# schemetic.net
KiCad netlist of a schematic drawn in Altium Designer
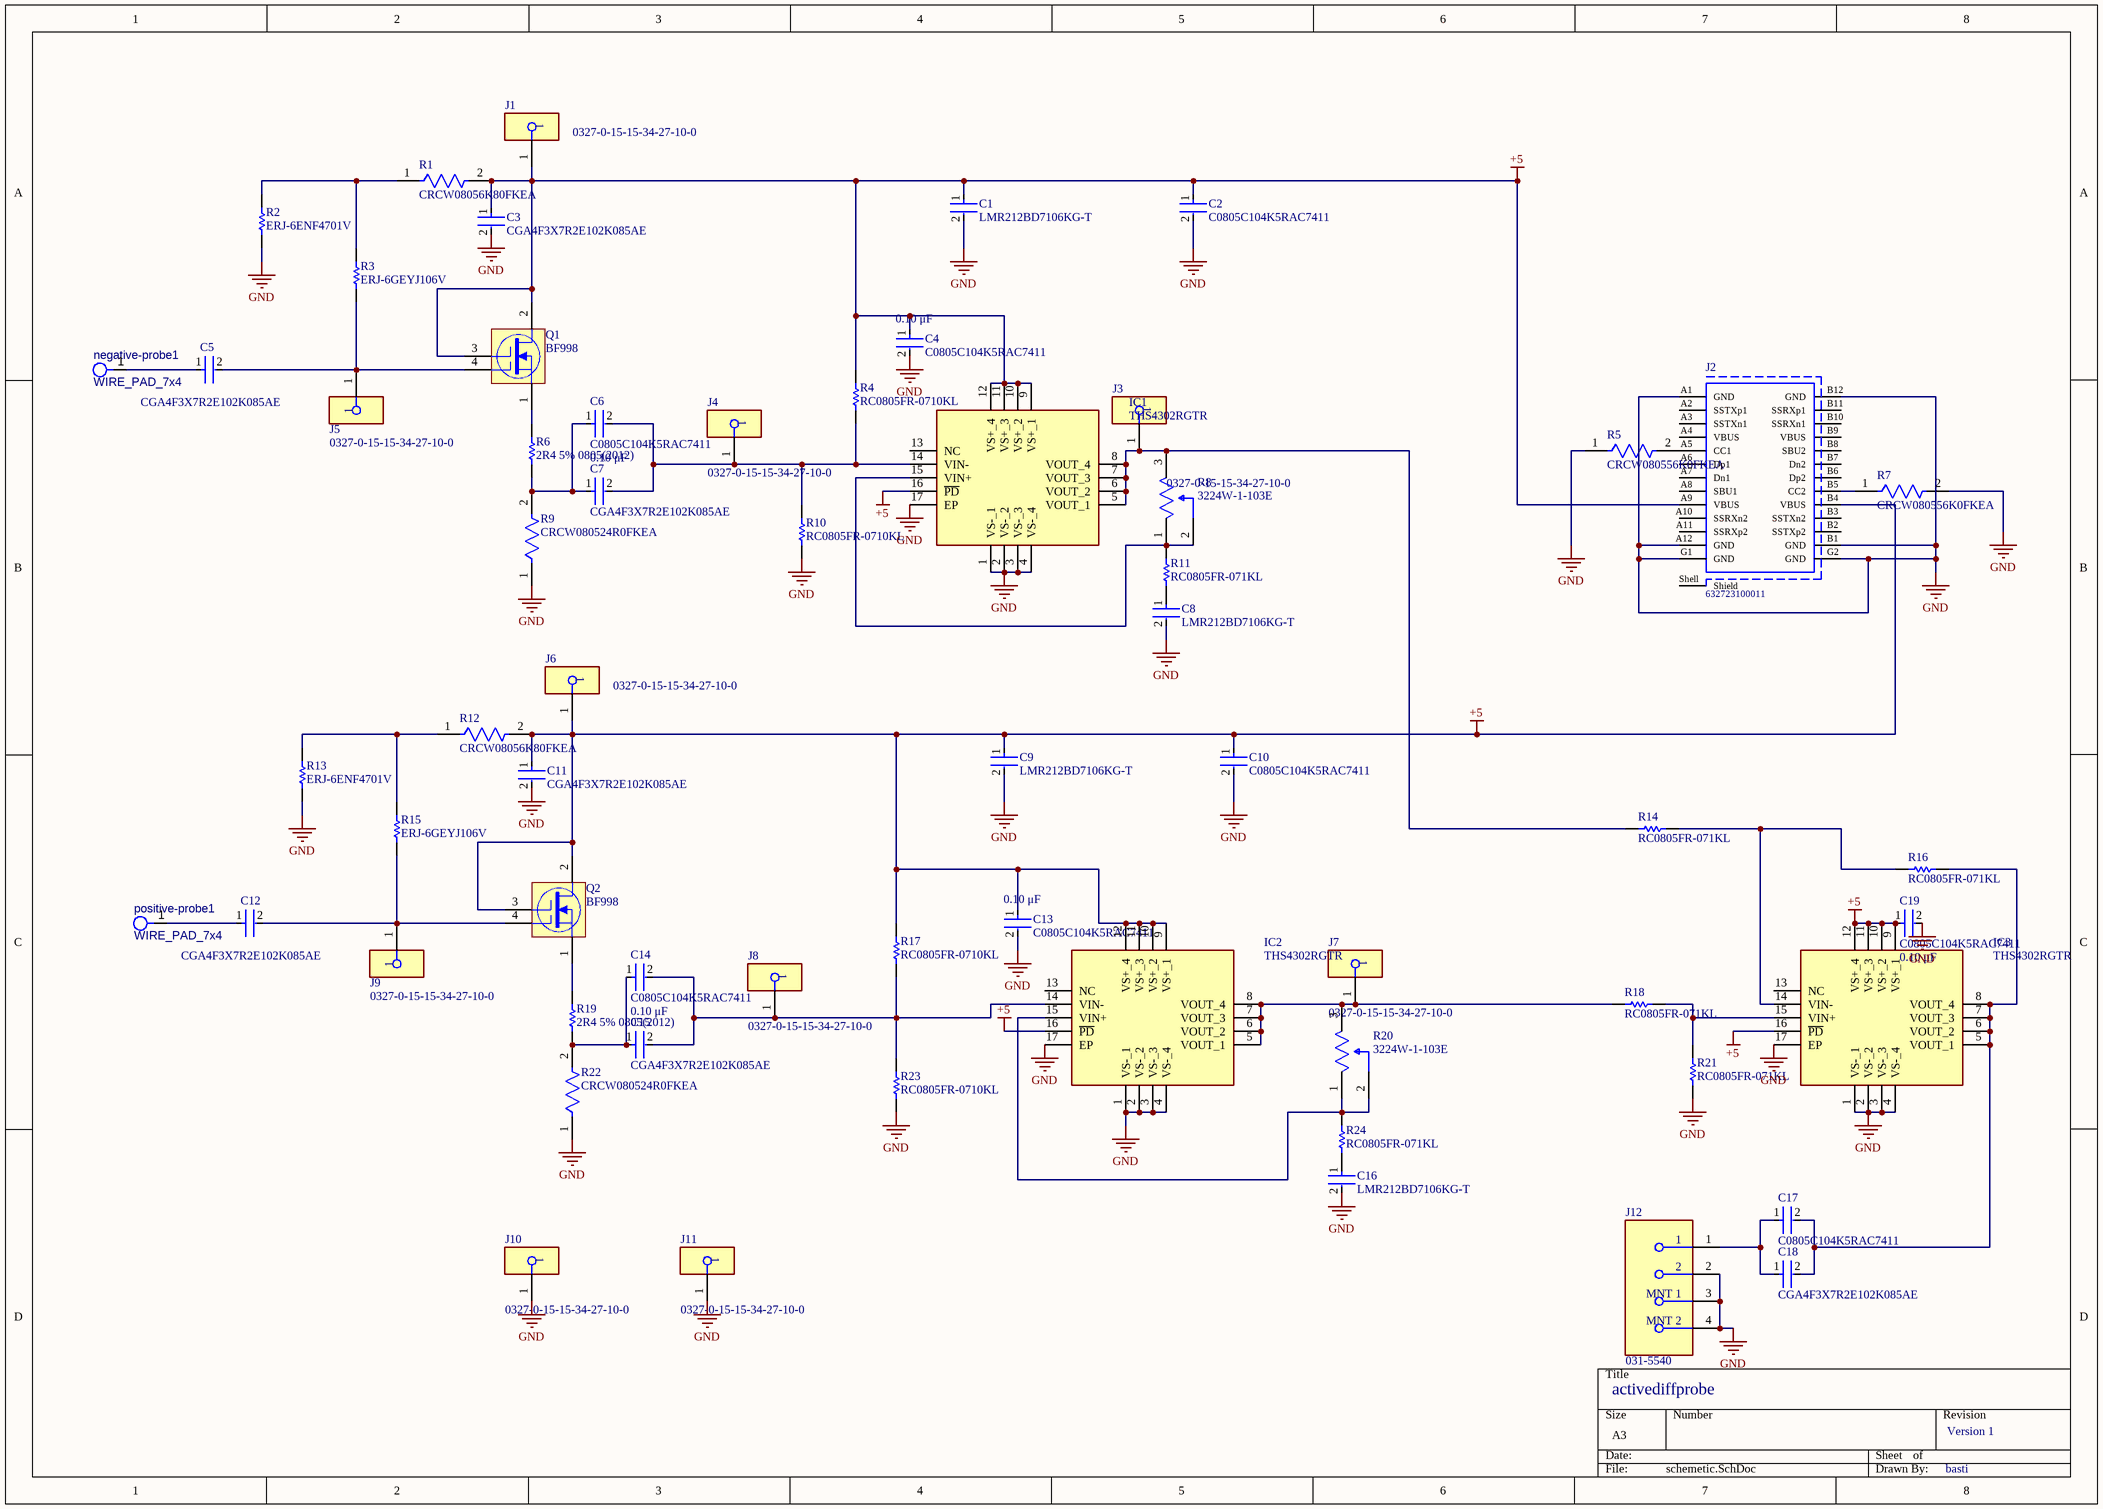
[diagram p0: schemetic.SchDoc]

(export (version "E")
  (design (tool "Eeschema 10.0.6"))
  (components
    (comp (ref "C1")
      (value "LMR212BD7106KG-T")
      (footprint "FP-0805-L_2_0_0_2-W_1_25-IPC_C")
      (description "Multilayer Ceramic Capacitor 10uF 10V X7T 10% SMD 0805 Automotive T/R")
      (libsource (lib "Altium Content Vault") (part "02cd4be3c70576c341d710602a673aa"))
    )
    (comp (ref "C2")
      (value "C0805C104K5RAC7411")
      (footprint "FP-C0805C-DN-MFG")
      (description "C0805 0.10 μF X7R 30ppm/°C 10.00% 50 V")
      (fields (field (name "MANUFACTURER") "KEMET") (field (name "TOLERANCE") "0.1"))
      (libsource (lib "Altium Content Vault") (part "b4654b650e69147ec39a6b967a45e02"))
    )
    (comp (ref "C3")
      (value "CGA4F3X7R2E102K085AE")
      (footprint "FP-CGA4J-IPC_B")
      (description "Cap Ceramic 1nF 250V X7R 10% Pad SMD 0805 +125°C Automotive T/R")
      (fields (field (name "TOLERANCE") "10%"))
      (libsource (lib "Altium Content Vault") (part "b4654b650e69147ec39a6b967a45e02"))
    )
    (comp (ref "C4")
      (value "C0805C104K5RAC7411")
      (footprint "FP-C0805C-DN-MFG")
      (description "C0805 0.10 μF X7R 30ppm/°C 10.00% 50 V")
      (fields
        (field (name "MANUFACTURER") "KEMET")
        (field (name "TOLERANCE") "0.1")
        (field (name "ALTIUM_VALUE") "0.10 μF")
      )
      (libsource (lib "Altium Content Vault") (part "b4654b650e69147ec39a6b967a45e02"))
    )
    (comp (ref "C5")
      (value "CGA4F3X7R2E102K085AE")
      (footprint "FP-CGA4J-IPC_B")
      (description "Cap Ceramic 1nF 250V X7R 10% Pad SMD 0805 +125°C Automotive T/R")
      (fields (field (name "TOLERANCE") "10%"))
      (libsource (lib "Altium Content Vault") (part "b4654b650e69147ec39a6b967a45e02"))
    )
    (comp (ref "C6")
      (value "C0805C104K5RAC7411")
      (footprint "FP-C0805C-DN-MFG")
      (description "C0805 0.10 μF X7R 30ppm/°C 10.00% 50 V")
      (fields
        (field (name "MANUFACTURER") "KEMET")
        (field (name "TOLERANCE") "0.1")
        (field (name "ALTIUM_VALUE") "0.10 μF")
      )
      (libsource (lib "Altium Content Vault") (part "b4654b650e69147ec39a6b967a45e02"))
    )
    (comp (ref "C7")
      (value "CGA4F3X7R2E102K085AE")
      (footprint "FP-CGA4J-IPC_B")
      (description "Cap Ceramic 1nF 250V X7R 10% Pad SMD 0805 +125°C Automotive T/R")
      (fields (field (name "TOLERANCE") "10%"))
      (libsource (lib "Altium Content Vault") (part "b4654b650e69147ec39a6b967a45e02"))
    )
    (comp (ref "C8")
      (value "LMR212BD7106KG-T")
      (footprint "FP-0805-L_2_0_0_2-W_1_25-IPC_C")
      (description "Multilayer Ceramic Capacitor 10uF 10V X7T 10% SMD 0805 Automotive T/R")
      (libsource (lib "Altium Content Vault") (part "02cd4be3c70576c341d710602a673aa"))
    )
    (comp (ref "C9")
      (value "LMR212BD7106KG-T")
      (footprint "FP-0805-L_2_0_0_2-W_1_25-IPC_C")
      (description "Multilayer Ceramic Capacitor 10uF 10V X7T 10% SMD 0805 Automotive T/R")
      (libsource (lib "Altium Content Vault") (part "02cd4be3c70576c341d710602a673aa"))
    )
    (comp (ref "C10")
      (value "C0805C104K5RAC7411")
      (footprint "FP-C0805C-DN-MFG")
      (description "C0805 0.10 μF X7R 30ppm/°C 10.00% 50 V")
      (fields (field (name "MANUFACTURER") "KEMET") (field (name "TOLERANCE") "0.1"))
      (libsource (lib "Altium Content Vault") (part "b4654b650e69147ec39a6b967a45e02"))
    )
    (comp (ref "C11")
      (value "CGA4F3X7R2E102K085AE")
      (footprint "FP-CGA4J-IPC_B")
      (description "Cap Ceramic 1nF 250V X7R 10% Pad SMD 0805 +125°C Automotive T/R")
      (fields (field (name "TOLERANCE") "10%"))
      (libsource (lib "Altium Content Vault") (part "b4654b650e69147ec39a6b967a45e02"))
    )
    (comp (ref "C12")
      (value "CGA4F3X7R2E102K085AE")
      (footprint "FP-CGA4J-IPC_B")
      (description "Cap Ceramic 1nF 250V X7R 10% Pad SMD 0805 +125°C Automotive T/R")
      (fields (field (name "TOLERANCE") "10%"))
      (libsource (lib "Altium Content Vault") (part "b4654b650e69147ec39a6b967a45e02"))
    )
    (comp (ref "C13")
      (value "C0805C104K5RAC7411")
      (footprint "FP-C0805C-DN-MFG")
      (description "C0805 0.10 μF X7R 30ppm/°C 10.00% 50 V")
      (fields
        (field (name "MANUFACTURER") "KEMET")
        (field (name "TOLERANCE") "0.1")
        (field (name "ALTIUM_VALUE") "0.10 μF")
      )
      (libsource (lib "Altium Content Vault") (part "b4654b650e69147ec39a6b967a45e02"))
    )
    (comp (ref "C14")
      (value "C0805C104K5RAC7411")
      (footprint "FP-C0805C-DN-MFG")
      (description "C0805 0.10 μF X7R 30ppm/°C 10.00% 50 V")
      (fields
        (field (name "MANUFACTURER") "KEMET")
        (field (name "TOLERANCE") "0.1")
        (field (name "ALTIUM_VALUE") "0.10 μF")
      )
      (libsource (lib "Altium Content Vault") (part "b4654b650e69147ec39a6b967a45e02"))
    )
    (comp (ref "C15")
      (value "CGA4F3X7R2E102K085AE")
      (footprint "FP-CGA4J-IPC_B")
      (description "Cap Ceramic 1nF 250V X7R 10% Pad SMD 0805 +125°C Automotive T/R")
      (fields (field (name "TOLERANCE") "10%"))
      (libsource (lib "Altium Content Vault") (part "b4654b650e69147ec39a6b967a45e02"))
    )
    (comp (ref "C16")
      (value "LMR212BD7106KG-T")
      (footprint "FP-0805-L_2_0_0_2-W_1_25-IPC_C")
      (description "Multilayer Ceramic Capacitor 10uF 10V X7T 10% SMD 0805 Automotive T/R")
      (libsource (lib "Altium Content Vault") (part "02cd4be3c70576c341d710602a673aa"))
    )
    (comp (ref "C17")
      (value "C0805C104K5RAC7411")
      (footprint "FP-C0805C-DN-MFG")
      (description "C0805 0.10 μF X7R 30ppm/°C 10.00% 50 V")
      (fields (field (name "MANUFACTURER") "KEMET") (field (name "TOLERANCE") "0.1"))
      (libsource (lib "Altium Content Vault") (part "b4654b650e69147ec39a6b967a45e02"))
    )
    (comp (ref "C18")
      (value "CGA4F3X7R2E102K085AE")
      (footprint "FP-CGA4J-IPC_B")
      (description "Cap Ceramic 1nF 250V X7R 10% Pad SMD 0805 +125°C Automotive T/R")
      (fields (field (name "TOLERANCE") "10%"))
      (libsource (lib "Altium Content Vault") (part "b4654b650e69147ec39a6b967a45e02"))
    )
    (comp (ref "C19")
      (value "C0805C104K5RAC7411")
      (footprint "FP-C0805C-DN-MFG")
      (description "C0805 0.10 μF X7R 30ppm/°C 10.00% 50 V")
      (fields
        (field (name "MANUFACTURER") "KEMET")
        (field (name "TOLERANCE") "0.1")
        (field (name "ALTIUM_VALUE") "0.10 μF")
      )
      (libsource (lib "Altium Content Vault") (part "b4654b650e69147ec39a6b967a45e02"))
    )
    (comp (ref "IC1")
      (value "THS4302RGTR")
      (footprint "SamacSys:QFN50P300X300X100-17N-D")
      (description "Integrated Circuit")
      (libsource (lib "*") (part "THS4302RGTR"))
    )
    (comp (ref "IC2")
      (value "THS4302RGTR")
      (footprint "SamacSys:QFN50P300X300X100-17N-D")
      (description "Integrated Circuit")
      (libsource (lib "*") (part "THS4302RGTR"))
    )
    (comp (ref "IC3")
      (value "THS4302RGTR")
      (footprint "SamacSys:QFN50P300X300X100-17N-D")
      (description "Integrated Circuit")
      (libsource (lib "*") (part "THS4302RGTR"))
    )
    (comp (ref "J1")
      (value "0327-0-15-15-34-27-10-0")
      (footprint "FP-0327-0-15-15-34-27-10-MFG")
      (description "CONN PIN RCPT .032-.046 SOLDER")
      (libsource (lib "Altium Content Vault") (part "c5c826e0c4b67fe3b42ef77f2d4decc"))
    )
    (comp (ref "J2")
      (value "632723100011")
      (footprint "632723100011")
      (description "USB 3.1 Type C Receptacle WR-COM, Horizontal, SMT / THT")
      (fields (field (name "MANUFACTURER") "Wurth Elektronik") (field (name "PUBLISHER") "WurthElektronik"))
      (libsource (lib "Altium Content Vault") (part "WE-632723X00011"))
    )
    (comp (ref "J3")
      (value "0327-0-15-15-34-27-10-0")
      (footprint "FP-0327-0-15-15-34-27-10-MFG")
      (description "CONN PIN RCPT .032-.046 SOLDER")
      (libsource (lib "Altium Content Vault") (part "c5c826e0c4b67fe3b42ef77f2d4decc"))
    )
    (comp (ref "J4")
      (value "0327-0-15-15-34-27-10-0")
      (footprint "FP-0327-0-15-15-34-27-10-MFG")
      (description "CONN PIN RCPT .032-.046 SOLDER")
      (libsource (lib "Altium Content Vault") (part "c5c826e0c4b67fe3b42ef77f2d4decc"))
    )
    (comp (ref "J5")
      (value "0327-0-15-15-34-27-10-0")
      (footprint "FP-0327-0-15-15-34-27-10-MFG")
      (description "CONN PIN RCPT .032-.046 SOLDER")
      (libsource (lib "") (part "c5c826e0c4b67fe3b42ef77f2d4decc_1"))
    )
    (comp (ref "J6")
      (value "0327-0-15-15-34-27-10-0")
      (footprint "FP-0327-0-15-15-34-27-10-MFG")
      (description "CONN PIN RCPT .032-.046 SOLDER")
      (libsource (lib "Altium Content Vault") (part "c5c826e0c4b67fe3b42ef77f2d4decc"))
    )
    (comp (ref "J7")
      (value "0327-0-15-15-34-27-10-0")
      (footprint "FP-0327-0-15-15-34-27-10-MFG")
      (description "CONN PIN RCPT .032-.046 SOLDER")
      (libsource (lib "Altium Content Vault") (part "c5c826e0c4b67fe3b42ef77f2d4decc"))
    )
    (comp (ref "J8")
      (value "0327-0-15-15-34-27-10-0")
      (footprint "FP-0327-0-15-15-34-27-10-MFG")
      (description "CONN PIN RCPT .032-.046 SOLDER")
      (libsource (lib "Altium Content Vault") (part "c5c826e0c4b67fe3b42ef77f2d4decc"))
    )
    (comp (ref "J9")
      (value "0327-0-15-15-34-27-10-0")
      (footprint "FP-0327-0-15-15-34-27-10-MFG")
      (description "CONN PIN RCPT .032-.046 SOLDER")
      (libsource (lib "") (part "c5c826e0c4b67fe3b42ef77f2d4decc_1"))
    )
    (comp (ref "J10")
      (value "0327-0-15-15-34-27-10-0")
      (footprint "FP-0327-0-15-15-34-27-10-MFG")
      (description "CONN PIN RCPT .032-.046 SOLDER")
      (libsource (lib "Altium Content Vault") (part "c5c826e0c4b67fe3b42ef77f2d4decc"))
    )
    (comp (ref "J11")
      (value "0327-0-15-15-34-27-10-0")
      (footprint "FP-0327-0-15-15-34-27-10-MFG")
      (description "CONN PIN RCPT .032-.046 SOLDER")
      (libsource (lib "Altium Content Vault") (part "c5c826e0c4b67fe3b42ef77f2d4decc"))
    )
    (comp (ref "J12")
      (value "031-5540")
      (footprint "FP-031-5540-MFG")
      (description "CONN BNC RCPT R/A 50 OHM PCB")
      (fields
        (field (name "OCTOPART") "https://octopart.com/031-5540-amphenol+rf-49742301")
        (field (name "MANUFACTURER") "Amphenol RF")
      )
      (libsource (lib "Altium Content Vault") (part "c4223d6e67c9a5a609df11ee682ef75"))
    )
    (comp (ref "negative-probe1")
      (value "WIRE_PAD_7x4")
      (footprint "WIRE_PAD_7x4-Footprint-1")
      (description "SMD WIRE PAD 7 x 4 mm")
      (libsource (lib "Joel Rupp") (part "CMP-001-0023-7"))
    )
    (comp (ref "positive-probe1")
      (value "WIRE_PAD_7x4")
      (footprint "WIRE_PAD_7x4-Footprint-1")
      (description "SMD WIRE PAD 7 x 4 mm")
      (libsource (lib "Joel Rupp") (part "CMP-001-0023-7"))
    )
    (comp (ref "Q1")
      (value "BF998")
      (footprint "INF-SOT143-4-1_V")
      (description "Silicon N-Channel MOSFET Tetrode, 30 mA ID, 20 dB Gp, SOT143-4-1, Green")
      (fields (field (name "MANUFACTURER") "Infineon"))
      (libsource (lib "Altium Content Vault") (part "INF-BF998-4"))
    )
    (comp (ref "Q2")
      (value "BF998")
      (footprint "INF-SOT143-4-1_V")
      (description "Silicon N-Channel MOSFET Tetrode, 30 mA ID, 20 dB Gp, SOT143-4-1, Green")
      (fields (field (name "MANUFACTURER") "Infineon"))
      (libsource (lib "Altium Content Vault") (part "INF-BF998-4"))
    )
    (comp (ref "R1")
      (value "CRCW08056K80FKEA")
      (footprint "FP-CRCW0805-e3-IPC_A")
      (description "RES Thick Film, 6.8kΩ, 1%, 0.125W, 100ppm/°C, 0805")
      (fields (field (name "TOLERANCE") "1%"))
      (libsource (lib "Altium Content Vault") (part "1029c3af85768c4190bb7ad29bc67b5"))
    )
    (comp (ref "R2")
      (value "ERJ-6ENF4701V")
      (footprint "RESC2013X70X40NL20T20")
      (description "Chip Resistor, 4.7 KOhm, +/- 1%, 0.125 W, -55 to 155 degC, 0805 (2012 Metric), RoHS, Tape and Reel")
      (fields (field (name "MANUFACTURER") "Panasonic"))
      (libsource (lib "Altium Content Vault") (part "RES-2"))
    )
    (comp (ref "R3")
      (value "ERJ-6GEYJ106V")
      (footprint "RESC2013X70X40LL20T20")
      (description "10MOhm")
      (fields (field (name "MANUFACTURER") "Panasonic"))
      (libsource (lib "Altium Content Vault") (part "RES"))
    )
    (comp (ref "R4")
      (value "RC0805FR-0710KL")
      (footprint "RESC2013X60X35NL10T20")
      (description "Chip Resistor, 10 KOhm, +/- 1%, 0.125 W, -55 to 155 degC, 0805 (2012 Metric), RoHS, Tape and Reel")
      (fields (field (name "MANUFACTURER") "Yageo"))
      (libsource (lib "Altium Content Vault") (part "RES-2"))
    )
    (comp (ref "R5")
      (value "CRCW080556K0FKEA")
      (footprint "FP-CRCW0805-e3-IPC_B")
      (description "RES Thick Film, 56kΩ, 1%, 0.125W, 100ppm/°C, 0805")
      (fields (field (name "TOLERANCE") "1%"))
      (libsource (lib "Altium Content Vault") (part "1029c3af85768c4190bb7ad29bc67b5"))
    )
    (comp (ref "R6")
      (value "2R4 5% 0805(2012)")
      (footprint "RESC0805(2012)_L")
      (description "2R4 0.125W 5% 0805 (2012 Metric)  SMD")
      (fields (field (name "POWER") "0.125 W") (field (name "TOLERANCE") "5 %"))
      (libsource (lib "Altium Content Vault") (part "RES"))
    )
    (comp (ref "R7")
      (value "CRCW080556K0FKEA")
      (footprint "FP-CRCW0805-e3-IPC_B")
      (description "RES Thick Film, 56kΩ, 1%, 0.125W, 100ppm/°C, 0805")
      (fields (field (name "TOLERANCE") "1%"))
      (libsource (lib "Altium Content Vault") (part "1029c3af85768c4190bb7ad29bc67b5"))
    )
    (comp (ref "R8")
      (value "3224W-1-103E")
      (footprint "FP-3224W-MFG")
      (description "TRIMMER 10K OHM 0.25W J LEAD TOP")
      (fields (field (name "TOLERANCE") "10%") (field (name "MANUFACTURER") "Bourns"))
      (libsource (lib "Altium Content Vault") (part "83d3d349ed884d1db45cec512f27eb6"))
    )
    (comp (ref "R9")
      (value "CRCW080524R0FKEA")
      (footprint "FP-CRCW0805-e3-MFG")
      (description "RES Thick Film, 24Ω, 1%, 0.125W, 100ppm/°C, 0805")
      (fields (field (name "TOLERANCE") "1%"))
      (libsource (lib "Altium Content Vault") (part "1029c3af85768c4190bb7ad29bc67b5"))
    )
    (comp (ref "R10")
      (value "RC0805FR-0710KL")
      (footprint "RESC2013X60X35NL10T20")
      (description "Chip Resistor, 10 KOhm, +/- 1%, 0.125 W, -55 to 155 degC, 0805 (2012 Metric), RoHS, Tape and Reel")
      (fields (field (name "MANUFACTURER") "Yageo"))
      (libsource (lib "Altium Content Vault") (part "RES-2"))
    )
    (comp (ref "R11")
      (value "RC0805FR-071KL")
      (footprint "RESC2013X60X35ML10T20")
      (description "Chip Resistor, 1 KOhm, +/- 1%, 125 mW, -55 to 155 degC, 0805 (2012 Metric), RoHS, Tape and Reel")
      (fields (field (name "TOLERANCE") "1%") (field (name "MANUFACTURER") "Yageo"))
      (libsource (lib "Altium Content Vault") (part "RES-2"))
    )
    (comp (ref "R12")
      (value "CRCW08056K80FKEA")
      (footprint "FP-CRCW0805-e3-IPC_A")
      (description "RES Thick Film, 6.8kΩ, 1%, 0.125W, 100ppm/°C, 0805")
      (fields (field (name "TOLERANCE") "1%"))
      (libsource (lib "Altium Content Vault") (part "1029c3af85768c4190bb7ad29bc67b5"))
    )
    (comp (ref "R13")
      (value "ERJ-6ENF4701V")
      (footprint "RESC2013X70X40NL20T20")
      (description "Chip Resistor, 4.7 KOhm, +/- 1%, 0.125 W, -55 to 155 degC, 0805 (2012 Metric), RoHS, Tape and Reel")
      (fields (field (name "MANUFACTURER") "Panasonic"))
      (libsource (lib "Altium Content Vault") (part "RES-2"))
    )
    (comp (ref "R14")
      (value "RC0805FR-071KL")
      (footprint "RESC2013X60X35ML10T20")
      (description "Chip Resistor, 1 KOhm, +/- 1%, 125 mW, -55 to 155 degC, 0805 (2012 Metric), RoHS, Tape and Reel")
      (fields (field (name "TOLERANCE") "1%") (field (name "MANUFACTURER") "Yageo"))
      (libsource (lib "Altium Content Vault") (part "RES-2"))
    )
    (comp (ref "R15")
      (value "ERJ-6GEYJ106V")
      (footprint "RESC2013X70X40LL20T20")
      (description "10MOhm")
      (fields (field (name "MANUFACTURER") "Panasonic"))
      (libsource (lib "Altium Content Vault") (part "RES"))
    )
    (comp (ref "R16")
      (value "RC0805FR-071KL")
      (footprint "RESC2013X60X35ML10T20")
      (description "Chip Resistor, 1 KOhm, +/- 1%, 125 mW, -55 to 155 degC, 0805 (2012 Metric), RoHS, Tape and Reel")
      (fields (field (name "TOLERANCE") "1%") (field (name "MANUFACTURER") "Yageo"))
      (libsource (lib "Altium Content Vault") (part "RES-2"))
    )
    (comp (ref "R17")
      (value "RC0805FR-0710KL")
      (footprint "RESC2013X60X35NL10T20")
      (description "Chip Resistor, 10 KOhm, +/- 1%, 0.125 W, -55 to 155 degC, 0805 (2012 Metric), RoHS, Tape and Reel")
      (fields (field (name "MANUFACTURER") "Yageo"))
      (libsource (lib "Altium Content Vault") (part "RES-2"))
    )
    (comp (ref "R18")
      (value "RC0805FR-071KL")
      (footprint "RESC2013X60X35ML10T20")
      (description "Chip Resistor, 1 KOhm, +/- 1%, 125 mW, -55 to 155 degC, 0805 (2012 Metric), RoHS, Tape and Reel")
      (fields (field (name "TOLERANCE") "1%") (field (name "MANUFACTURER") "Yageo"))
      (libsource (lib "Altium Content Vault") (part "RES-2"))
    )
    (comp (ref "R19")
      (value "2R4 5% 0805(2012)")
      (footprint "RESC0805(2012)_L")
      (description "2R4 0.125W 5% 0805 (2012 Metric)  SMD")
      (fields (field (name "POWER") "0.125 W") (field (name "TOLERANCE") "5 %"))
      (libsource (lib "Altium Content Vault") (part "RES"))
    )
    (comp (ref "R20")
      (value "3224W-1-103E")
      (footprint "FP-3224W-MFG")
      (description "TRIMMER 10K OHM 0.25W J LEAD TOP")
      (fields (field (name "TOLERANCE") "10%") (field (name "MANUFACTURER") "Bourns"))
      (libsource (lib "Altium Content Vault") (part "83d3d349ed884d1db45cec512f27eb6"))
    )
    (comp (ref "R21")
      (value "RC0805FR-071KL")
      (footprint "RESC2013X60X35ML10T20")
      (description "Chip Resistor, 1 KOhm, +/- 1%, 125 mW, -55 to 155 degC, 0805 (2012 Metric), RoHS, Tape and Reel")
      (fields (field (name "TOLERANCE") "1%") (field (name "MANUFACTURER") "Yageo"))
      (libsource (lib "Altium Content Vault") (part "RES-2"))
    )
    (comp (ref "R22")
      (value "CRCW080524R0FKEA")
      (footprint "FP-CRCW0805-e3-MFG")
      (description "RES Thick Film, 24Ω, 1%, 0.125W, 100ppm/°C, 0805")
      (fields (field (name "TOLERANCE") "1%"))
      (libsource (lib "Altium Content Vault") (part "1029c3af85768c4190bb7ad29bc67b5"))
    )
    (comp (ref "R23")
      (value "RC0805FR-0710KL")
      (footprint "RESC2013X60X35NL10T20")
      (description "Chip Resistor, 10 KOhm, +/- 1%, 0.125 W, -55 to 155 degC, 0805 (2012 Metric), RoHS, Tape and Reel")
      (fields (field (name "MANUFACTURER") "Yageo"))
      (libsource (lib "Altium Content Vault") (part "RES-2"))
    )
    (comp (ref "R24")
      (value "RC0805FR-071KL")
      (footprint "RESC2013X60X35ML10T20")
      (description "Chip Resistor, 1 KOhm, +/- 1%, 125 mW, -55 to 155 degC, 0805 (2012 Metric), RoHS, Tape and Reel")
      (fields (field (name "TOLERANCE") "1%") (field (name "MANUFACTURER") "Yageo"))
      (libsource (lib "Altium Content Vault") (part "RES-2"))
    )
  )
  (nets
    (net (code "1") (name "+5") (class "Default")
      (node (ref "C1") (pin "1") (pinfunction "1_1") (pintype "passive"))
      (node (ref "C10") (pin "1") (pinfunction "1_1") (pintype "passive"))
      (node (ref "C11") (pin "1") (pinfunction "1_1") (pintype "passive"))
      (node (ref "C13") (pin "1") (pinfunction "1_1") (pintype "passive"))
      (node (ref "C19") (pin "1") (pinfunction "1_1") (pintype "passive"))
      (node (ref "C2") (pin "1") (pinfunction "1_1") (pintype "passive"))
      (node (ref "C3") (pin "1") (pinfunction "1_1") (pintype "passive"))
      (node (ref "C4") (pin "1") (pinfunction "1_1") (pintype "passive"))
      (node (ref "C9") (pin "1") (pinfunction "1_1") (pintype "passive"))
      (node (ref "IC1") (pin "10") (pinfunction "VS+_2_10") (pintype "passive"))
      (node (ref "IC1") (pin "11") (pinfunction "VS+_3_11") (pintype "passive"))
      (node (ref "IC1") (pin "12") (pinfunction "VS+_4_12") (pintype "passive"))
      (node (ref "IC1") (pin "16") (pinfunction "~{PD}_16") (pintype "passive"))
      (node (ref "IC1") (pin "9") (pinfunction "VS+_1_9") (pintype "passive"))
      (node (ref "IC2") (pin "10") (pinfunction "VS+_2_10") (pintype "passive"))
      (node (ref "IC2") (pin "11") (pinfunction "VS+_3_11") (pintype "passive"))
      (node (ref "IC2") (pin "12") (pinfunction "VS+_4_12") (pintype "passive"))
      (node (ref "IC2") (pin "16") (pinfunction "~{PD}_16") (pintype "passive"))
      (node (ref "IC2") (pin "9") (pinfunction "VS+_1_9") (pintype "passive"))
      (node (ref "IC3") (pin "10") (pinfunction "VS+_2_10") (pintype "passive"))
      (node (ref "IC3") (pin "11") (pinfunction "VS+_3_11") (pintype "passive"))
      (node (ref "IC3") (pin "12") (pinfunction "VS+_4_12") (pintype "passive"))
      (node (ref "IC3") (pin "16") (pinfunction "~{PD}_16") (pintype "passive"))
      (node (ref "IC3") (pin "9") (pinfunction "VS+_1_9") (pintype "passive"))
      (node (ref "J1") (pin "1") (pinfunction "1_1") (pintype "passive"))
      (node (ref "J2") (pin "A9") (pinfunction "VBUS_A9") (pintype "passive"))
      (node (ref "J2") (pin "B4") (pinfunction "VBUS_B4") (pintype "passive"))
      (node (ref "J6") (pin "1") (pinfunction "1_1") (pintype "passive"))
      (node (ref "Q1") (pin "2") (pinfunction "D_2") (pintype "passive"))
      (node (ref "Q1") (pin "3") (pinfunction "G2_3") (pintype "passive"))
      (node (ref "Q2") (pin "2") (pinfunction "D_2") (pintype "passive"))
      (node (ref "Q2") (pin "3") (pinfunction "G2_3") (pintype "passive"))
      (node (ref "R1") (pin "2") (pinfunction "2_2") (pintype "passive"))
      (node (ref "R12") (pin "2") (pinfunction "2_2") (pintype "passive"))
      (node (ref "R17") (pin "2") (pinfunction "2_2") (pintype "passive"))
      (node (ref "R4") (pin "2") (pinfunction "2_2") (pintype "passive"))
    )
    (net (code "2") (name "GND") (class "Default")
      (node (ref "C1") (pin "2") (pinfunction "2_2") (pintype "passive"))
      (node (ref "C10") (pin "2") (pinfunction "2_2") (pintype "passive"))
      (node (ref "C11") (pin "2") (pinfunction "2_2") (pintype "passive"))
      (node (ref "C13") (pin "2") (pinfunction "2_2") (pintype "passive"))
      (node (ref "C16") (pin "2") (pinfunction "2_2") (pintype "passive"))
      (node (ref "C19") (pin "2") (pinfunction "2_2") (pintype "passive"))
      (node (ref "C2") (pin "2") (pinfunction "2_2") (pintype "passive"))
      (node (ref "C3") (pin "2") (pinfunction "2_2") (pintype "passive"))
      (node (ref "C4") (pin "2") (pinfunction "2_2") (pintype "passive"))
      (node (ref "C8") (pin "2") (pinfunction "2_2") (pintype "passive"))
      (node (ref "C9") (pin "2") (pinfunction "2_2") (pintype "passive"))
      (node (ref "IC1") (pin "1") (pinfunction "VS-_1_1") (pintype "passive"))
      (node (ref "IC1") (pin "17") (pinfunction "EP_17") (pintype "passive"))
      (node (ref "IC1") (pin "2") (pinfunction "VS-_2_2") (pintype "passive"))
      (node (ref "IC1") (pin "3") (pinfunction "VS-_3_3") (pintype "passive"))
      (node (ref "IC1") (pin "4") (pinfunction "VS-_4_4") (pintype "passive"))
      (node (ref "IC2") (pin "1") (pinfunction "VS-_1_1") (pintype "passive"))
      (node (ref "IC2") (pin "17") (pinfunction "EP_17") (pintype "passive"))
      (node (ref "IC2") (pin "2") (pinfunction "VS-_2_2") (pintype "passive"))
      (node (ref "IC2") (pin "3") (pinfunction "VS-_3_3") (pintype "passive"))
      (node (ref "IC2") (pin "4") (pinfunction "VS-_4_4") (pintype "passive"))
      (node (ref "IC3") (pin "1") (pinfunction "VS-_1_1") (pintype "passive"))
      (node (ref "IC3") (pin "17") (pinfunction "EP_17") (pintype "passive"))
      (node (ref "IC3") (pin "2") (pinfunction "VS-_2_2") (pintype "passive"))
      (node (ref "IC3") (pin "3") (pinfunction "VS-_3_3") (pintype "passive"))
      (node (ref "IC3") (pin "4") (pinfunction "VS-_4_4") (pintype "passive"))
      (node (ref "J10") (pin "1") (pinfunction "1_1") (pintype "passive"))
      (node (ref "J11") (pin "1") (pinfunction "1_1") (pintype "passive"))
      (node (ref "J12") (pin "2") (pinfunction "2_2") (pintype "passive"))
      (node (ref "J12") (pin "3") (pinfunction "MNT_1_3") (pintype "passive"))
      (node (ref "J12") (pin "4") (pinfunction "MNT_2_4") (pintype "passive"))
      (node (ref "J2") (pin "A1") (pinfunction "GND_A1") (pintype "passive"))
      (node (ref "J2") (pin "A12") (pinfunction "GND_A12") (pintype "passive"))
      (node (ref "J2") (pin "B1") (pinfunction "GND_B1") (pintype "passive"))
      (node (ref "J2") (pin "B12") (pinfunction "GND_B12") (pintype "passive"))
      (node (ref "J2") (pin "G1") (pinfunction "GND_G1") (pintype "passive"))
      (node (ref "J2") (pin "G2") (pinfunction "GND_G2") (pintype "passive"))
      (node (ref "R10") (pin "1") (pinfunction "1_1") (pintype "passive"))
      (node (ref "R13") (pin "1") (pinfunction "1_1") (pintype "passive"))
      (node (ref "R2") (pin "1") (pinfunction "1_1") (pintype "passive"))
      (node (ref "R21") (pin "2") (pinfunction "2_2") (pintype "passive"))
      (node (ref "R22") (pin "1") (pinfunction "1_1") (pintype "passive"))
      (node (ref "R23") (pin "1") (pinfunction "1_1") (pintype "passive"))
      (node (ref "R5") (pin "1") (pinfunction "1_1") (pintype "passive"))
      (node (ref "R7") (pin "2") (pinfunction "2_2") (pintype "passive"))
      (node (ref "R9") (pin "1") (pinfunction "1_1") (pintype "passive"))
    )
    (net (code "3") (name "Net-(C6-Pad1)") (class "Default")
      (node (ref "C6") (pin "1") (pinfunction "1_1") (pintype "passive"))
      (node (ref "C7") (pin "1") (pinfunction "1_1") (pintype "passive"))
      (node (ref "R6") (pin "1") (pinfunction "1_1") (pintype "passive"))
      (node (ref "R9") (pin "2") (pinfunction "2_2") (pintype "passive"))
    )
    (net (code "4") (name "Net-(C8-Pad1)") (class "Default")
      (node (ref "C8") (pin "1") (pinfunction "1_1") (pintype "passive"))
      (node (ref "R11") (pin "1") (pinfunction "1_1") (pintype "passive"))
    )
    (net (code "5") (name "Net-(C14-Pad1)") (class "Default")
      (node (ref "C14") (pin "1") (pinfunction "1_1") (pintype "passive"))
      (node (ref "C15") (pin "1") (pinfunction "1_1") (pintype "passive"))
      (node (ref "R19") (pin "1") (pinfunction "1_1") (pintype "passive"))
      (node (ref "R22") (pin "2") (pinfunction "2_2") (pintype "passive"))
    )
    (net (code "6") (name "Net-(C16-Pad1)") (class "Default")
      (node (ref "C16") (pin "1") (pinfunction "1_1") (pintype "passive"))
      (node (ref "R24") (pin "1") (pinfunction "1_1") (pintype "passive"))
    )
    (net (code "7") (name "Net-(C17-Pad1)") (class "Default")
      (node (ref "C17") (pin "1") (pinfunction "1_1") (pintype "passive"))
      (node (ref "C18") (pin "1") (pinfunction "1_1") (pintype "passive"))
      (node (ref "J12") (pin "1") (pinfunction "1_1") (pintype "passive"))
    )
    (net (code "8") (name "Net-(IC1-VIN+)") (class "Default")
      (node (ref "IC1") (pin "15") (pinfunction "VIN+_15") (pintype "passive"))
      (node (ref "R11") (pin "2") (pinfunction "2_2") (pintype "passive"))
      (node (ref "R8") (pin "1") (pinfunction "CCW_1") (pintype "passive"))
      (node (ref "R8") (pin "2") (pinfunction "WIPER_2") (pintype "passive"))
    )
    (net (code "9") (name "Net-(IC1-VIN-)") (class "Default")
      (node (ref "C6") (pin "2") (pinfunction "2_2") (pintype "passive"))
      (node (ref "C7") (pin "2") (pinfunction "2_2") (pintype "passive"))
      (node (ref "IC1") (pin "14") (pinfunction "VIN-_14") (pintype "passive"))
      (node (ref "J4") (pin "1") (pinfunction "1_1") (pintype "passive"))
      (node (ref "R10") (pin "2") (pinfunction "2_2") (pintype "passive"))
      (node (ref "R4") (pin "1") (pinfunction "1_1") (pintype "passive"))
    )
    (net (code "10") (name "Net-(IC1-VOUT_1)") (class "Default")
      (node (ref "IC1") (pin "5") (pinfunction "VOUT_1_5") (pintype "passive"))
      (node (ref "IC1") (pin "6") (pinfunction "VOUT_2_6") (pintype "passive"))
      (node (ref "IC1") (pin "7") (pinfunction "VOUT_3_7") (pintype "passive"))
      (node (ref "IC1") (pin "8") (pinfunction "VOUT_4_8") (pintype "passive"))
      (node (ref "J3") (pin "1") (pinfunction "1_1") (pintype "passive"))
      (node (ref "R14") (pin "2") (pinfunction "2_2") (pintype "passive"))
      (node (ref "R8") (pin "3") (pinfunction "CW_3") (pintype "passive"))
    )
    (net (code "11") (name "Net-(IC2-VIN+)") (class "Default")
      (node (ref "IC2") (pin "15") (pinfunction "VIN+_15") (pintype "passive"))
      (node (ref "R20") (pin "1") (pinfunction "CCW_1") (pintype "passive"))
      (node (ref "R20") (pin "2") (pinfunction "WIPER_2") (pintype "passive"))
      (node (ref "R24") (pin "2") (pinfunction "2_2") (pintype "passive"))
    )
    (net (code "12") (name "Net-(IC2-VIN-)") (class "Default")
      (node (ref "C14") (pin "2") (pinfunction "2_2") (pintype "passive"))
      (node (ref "C15") (pin "2") (pinfunction "2_2") (pintype "passive"))
      (node (ref "IC2") (pin "14") (pinfunction "VIN-_14") (pintype "passive"))
      (node (ref "J8") (pin "1") (pinfunction "1_1") (pintype "passive"))
      (node (ref "R17") (pin "1") (pinfunction "1_1") (pintype "passive"))
      (node (ref "R23") (pin "2") (pinfunction "2_2") (pintype "passive"))
    )
    (net (code "13") (name "Net-(IC2-VOUT_1)") (class "Default")
      (node (ref "IC2") (pin "5") (pinfunction "VOUT_1_5") (pintype "passive"))
      (node (ref "IC2") (pin "6") (pinfunction "VOUT_2_6") (pintype "passive"))
      (node (ref "IC2") (pin "7") (pinfunction "VOUT_3_7") (pintype "passive"))
      (node (ref "IC2") (pin "8") (pinfunction "VOUT_4_8") (pintype "passive"))
      (node (ref "J7") (pin "1") (pinfunction "1_1") (pintype "passive"))
      (node (ref "R18") (pin "2") (pinfunction "2_2") (pintype "passive"))
      (node (ref "R20") (pin "3") (pinfunction "CW_3") (pintype "passive"))
    )
    (net (code "14") (name "Net-(IC3-VIN+)") (class "Default")
      (node (ref "IC3") (pin "15") (pinfunction "VIN+_15") (pintype "passive"))
      (node (ref "R18") (pin "1") (pinfunction "1_1") (pintype "passive"))
      (node (ref "R21") (pin "1") (pinfunction "1_1") (pintype "passive"))
    )
    (net (code "15") (name "Net-(IC3-VIN-)") (class "Default")
      (node (ref "IC3") (pin "14") (pinfunction "VIN-_14") (pintype "passive"))
      (node (ref "R14") (pin "1") (pinfunction "1_1") (pintype "passive"))
      (node (ref "R16") (pin "2") (pinfunction "2_2") (pintype "passive"))
    )
    (net (code "16") (name "Net-(IC3-VOUT_1)") (class "Default")
      (node (ref "C17") (pin "2") (pinfunction "2_2") (pintype "passive"))
      (node (ref "C18") (pin "2") (pinfunction "2_2") (pintype "passive"))
      (node (ref "IC3") (pin "5") (pinfunction "VOUT_1_5") (pintype "passive"))
      (node (ref "IC3") (pin "6") (pinfunction "VOUT_2_6") (pintype "passive"))
      (node (ref "IC3") (pin "7") (pinfunction "VOUT_3_7") (pintype "passive"))
      (node (ref "IC3") (pin "8") (pinfunction "VOUT_4_8") (pintype "passive"))
      (node (ref "R16") (pin "1") (pinfunction "1_1") (pintype "passive"))
    )
    (net (code "17") (name "Net-(J2-CC1)") (class "Default")
      (node (ref "J2") (pin "A5") (pinfunction "CC1_A5") (pintype "passive"))
      (node (ref "R5") (pin "2") (pinfunction "2_2") (pintype "passive"))
    )
    (net (code "18") (name "Net-(J2-CC2)") (class "Default")
      (node (ref "J2") (pin "B5") (pinfunction "CC2_B5") (pintype "passive"))
      (node (ref "R7") (pin "1") (pinfunction "1_1") (pintype "passive"))
    )
    (net (code "19") (name "Net-(Q1-G1)") (class "Default")
      (node (ref "C5") (pin "2") (pinfunction "2_2") (pintype "passive"))
      (node (ref "J5") (pin "1") (pinfunction "1_1") (pintype "passive"))
      (node (ref "Q1") (pin "4") (pinfunction "G1_4") (pintype "passive"))
      (node (ref "R3") (pin "1") (pinfunction "1_1") (pintype "passive"))
    )
    (net (code "20") (name "Net-(Q1-S)") (class "Default")
      (node (ref "Q1") (pin "1") (pinfunction "S_1") (pintype "passive"))
      (node (ref "R6") (pin "2") (pinfunction "2_2") (pintype "passive"))
    )
    (net (code "21") (name "Net-(Q2-G1)") (class "Default")
      (node (ref "C12") (pin "2") (pinfunction "2_2") (pintype "passive"))
      (node (ref "J9") (pin "1") (pinfunction "1_1") (pintype "passive"))
      (node (ref "Q2") (pin "4") (pinfunction "G1_4") (pintype "passive"))
      (node (ref "R15") (pin "1") (pinfunction "1_1") (pintype "passive"))
    )
    (net (code "22") (name "Net-(Q2-S)") (class "Default")
      (node (ref "Q2") (pin "1") (pinfunction "S_1") (pintype "passive"))
      (node (ref "R19") (pin "2") (pinfunction "2_2") (pintype "passive"))
    )
    (net (code "23") (name "Net-(R1-Pad1)") (class "Default")
      (node (ref "R1") (pin "1") (pinfunction "1_1") (pintype "passive"))
      (node (ref "R2") (pin "2") (pinfunction "2_2") (pintype "passive"))
      (node (ref "R3") (pin "2") (pinfunction "2_2") (pintype "passive"))
    )
    (net (code "24") (name "Net-(R12-Pad1)") (class "Default")
      (node (ref "R12") (pin "1") (pinfunction "1_1") (pintype "passive"))
      (node (ref "R13") (pin "2") (pinfunction "2_2") (pintype "passive"))
      (node (ref "R15") (pin "2") (pinfunction "2_2") (pintype "passive"))
    )
    (net (code "25") (name "Net-(negative-probe1-H1)") (class "Default")
      (node (ref "C5") (pin "1") (pinfunction "1_1") (pintype "passive"))
      (node (ref "negative-probe1") (pin "1") (pinfunction "H1_1") (pintype "passive"))
    )
    (net (code "26") (name "Net-(positive-probe1-H1)") (class "Default")
      (node (ref "C12") (pin "1") (pinfunction "1_1") (pintype "passive"))
      (node (ref "positive-probe1") (pin "1") (pinfunction "H1_1") (pintype "passive"))
    )
    (net (code "27") (name "unconnected-(IC1-NC-Pad13)") (class "Default")
      (node (ref "IC1") (pin "13") (pinfunction "NC_13") (pintype "passive"))
    )
    (net (code "28") (name "unconnected-(IC2-NC-Pad13)") (class "Default")
      (node (ref "IC2") (pin "13") (pinfunction "NC_13") (pintype "passive"))
    )
    (net (code "29") (name "unconnected-(IC3-NC-Pad13)") (class "Default")
      (node (ref "IC3") (pin "13") (pinfunction "NC_13") (pintype "passive"))
    )
    (net (code "30") (name "unconnected-(J2-Dn1-PadA7)") (class "Default")
      (node (ref "J2") (pin "A7") (pinfunction "Dn1_A7") (pintype "passive"))
    )
    (net (code "31") (name "unconnected-(J2-Dn2-PadB7)") (class "Default")
      (node (ref "J2") (pin "B7") (pinfunction "Dn2_B7") (pintype "passive"))
    )
    (net (code "32") (name "unconnected-(J2-Dp1-PadA6)") (class "Default")
      (node (ref "J2") (pin "A6") (pinfunction "Dp1_A6") (pintype "passive"))
    )
    (net (code "33") (name "unconnected-(J2-Dp2-PadB6)") (class "Default")
      (node (ref "J2") (pin "B6") (pinfunction "Dp2_B6") (pintype "passive"))
    )
    (net (code "34") (name "unconnected-(J2-SBU1-PadA8)") (class "Default")
      (node (ref "J2") (pin "A8") (pinfunction "SBU1_A8") (pintype "passive"))
    )
    (net (code "35") (name "unconnected-(J2-SBU2-PadB8)") (class "Default")
      (node (ref "J2") (pin "B8") (pinfunction "SBU2_B8") (pintype "passive"))
    )
    (net (code "36") (name "unconnected-(J2-SSRXn1-PadB10)") (class "Default")
      (node (ref "J2") (pin "B10") (pinfunction "SSRXn1_B10") (pintype "passive"))
    )
    (net (code "37") (name "unconnected-(J2-SSRXn2-PadA10)") (class "Default")
      (node (ref "J2") (pin "A10") (pinfunction "SSRXn2_A10") (pintype "passive"))
    )
    (net (code "38") (name "unconnected-(J2-SSRXp1-PadB11)") (class "Default")
      (node (ref "J2") (pin "B11") (pinfunction "SSRXp1_B11") (pintype "passive"))
    )
    (net (code "39") (name "unconnected-(J2-SSRXp2-PadA11)") (class "Default")
      (node (ref "J2") (pin "A11") (pinfunction "SSRXp2_A11") (pintype "passive"))
    )
    (net (code "40") (name "unconnected-(J2-SSTXn1-PadA3)") (class "Default")
      (node (ref "J2") (pin "A3") (pinfunction "SSTXn1_A3") (pintype "passive"))
    )
    (net (code "41") (name "unconnected-(J2-SSTXn2-PadB3)") (class "Default")
      (node (ref "J2") (pin "B3") (pinfunction "SSTXn2_B3") (pintype "passive"))
    )
    (net (code "42") (name "unconnected-(J2-SSTXp1-PadA2)") (class "Default")
      (node (ref "J2") (pin "A2") (pinfunction "SSTXp1_A2") (pintype "passive"))
    )
    (net (code "43") (name "unconnected-(J2-SSTXp2-PadB2)") (class "Default")
      (node (ref "J2") (pin "B2") (pinfunction "SSTXp2_B2") (pintype "passive"))
    )
    (net (code "44") (name "unconnected-(J2-Shield-PadShell)") (class "Default")
      (node (ref "J2") (pin "Shell") (pinfunction "Shield_Shell") (pintype "passive"))
    )
    (net (code "45") (name "unconnected-(J2-VBUS-PadA4)") (class "Default")
      (node (ref "J2") (pin "A4") (pinfunction "VBUS_A4") (pintype "passive"))
    )
    (net (code "46") (name "unconnected-(J2-VBUS-PadB9)") (class "Default")
      (node (ref "J2") (pin "B9") (pinfunction "VBUS_B9") (pintype "passive"))
    )
  )
)
